# Linkable_LED_Matrix.net
KiCad netlist of a schematic drawn in EAGLE
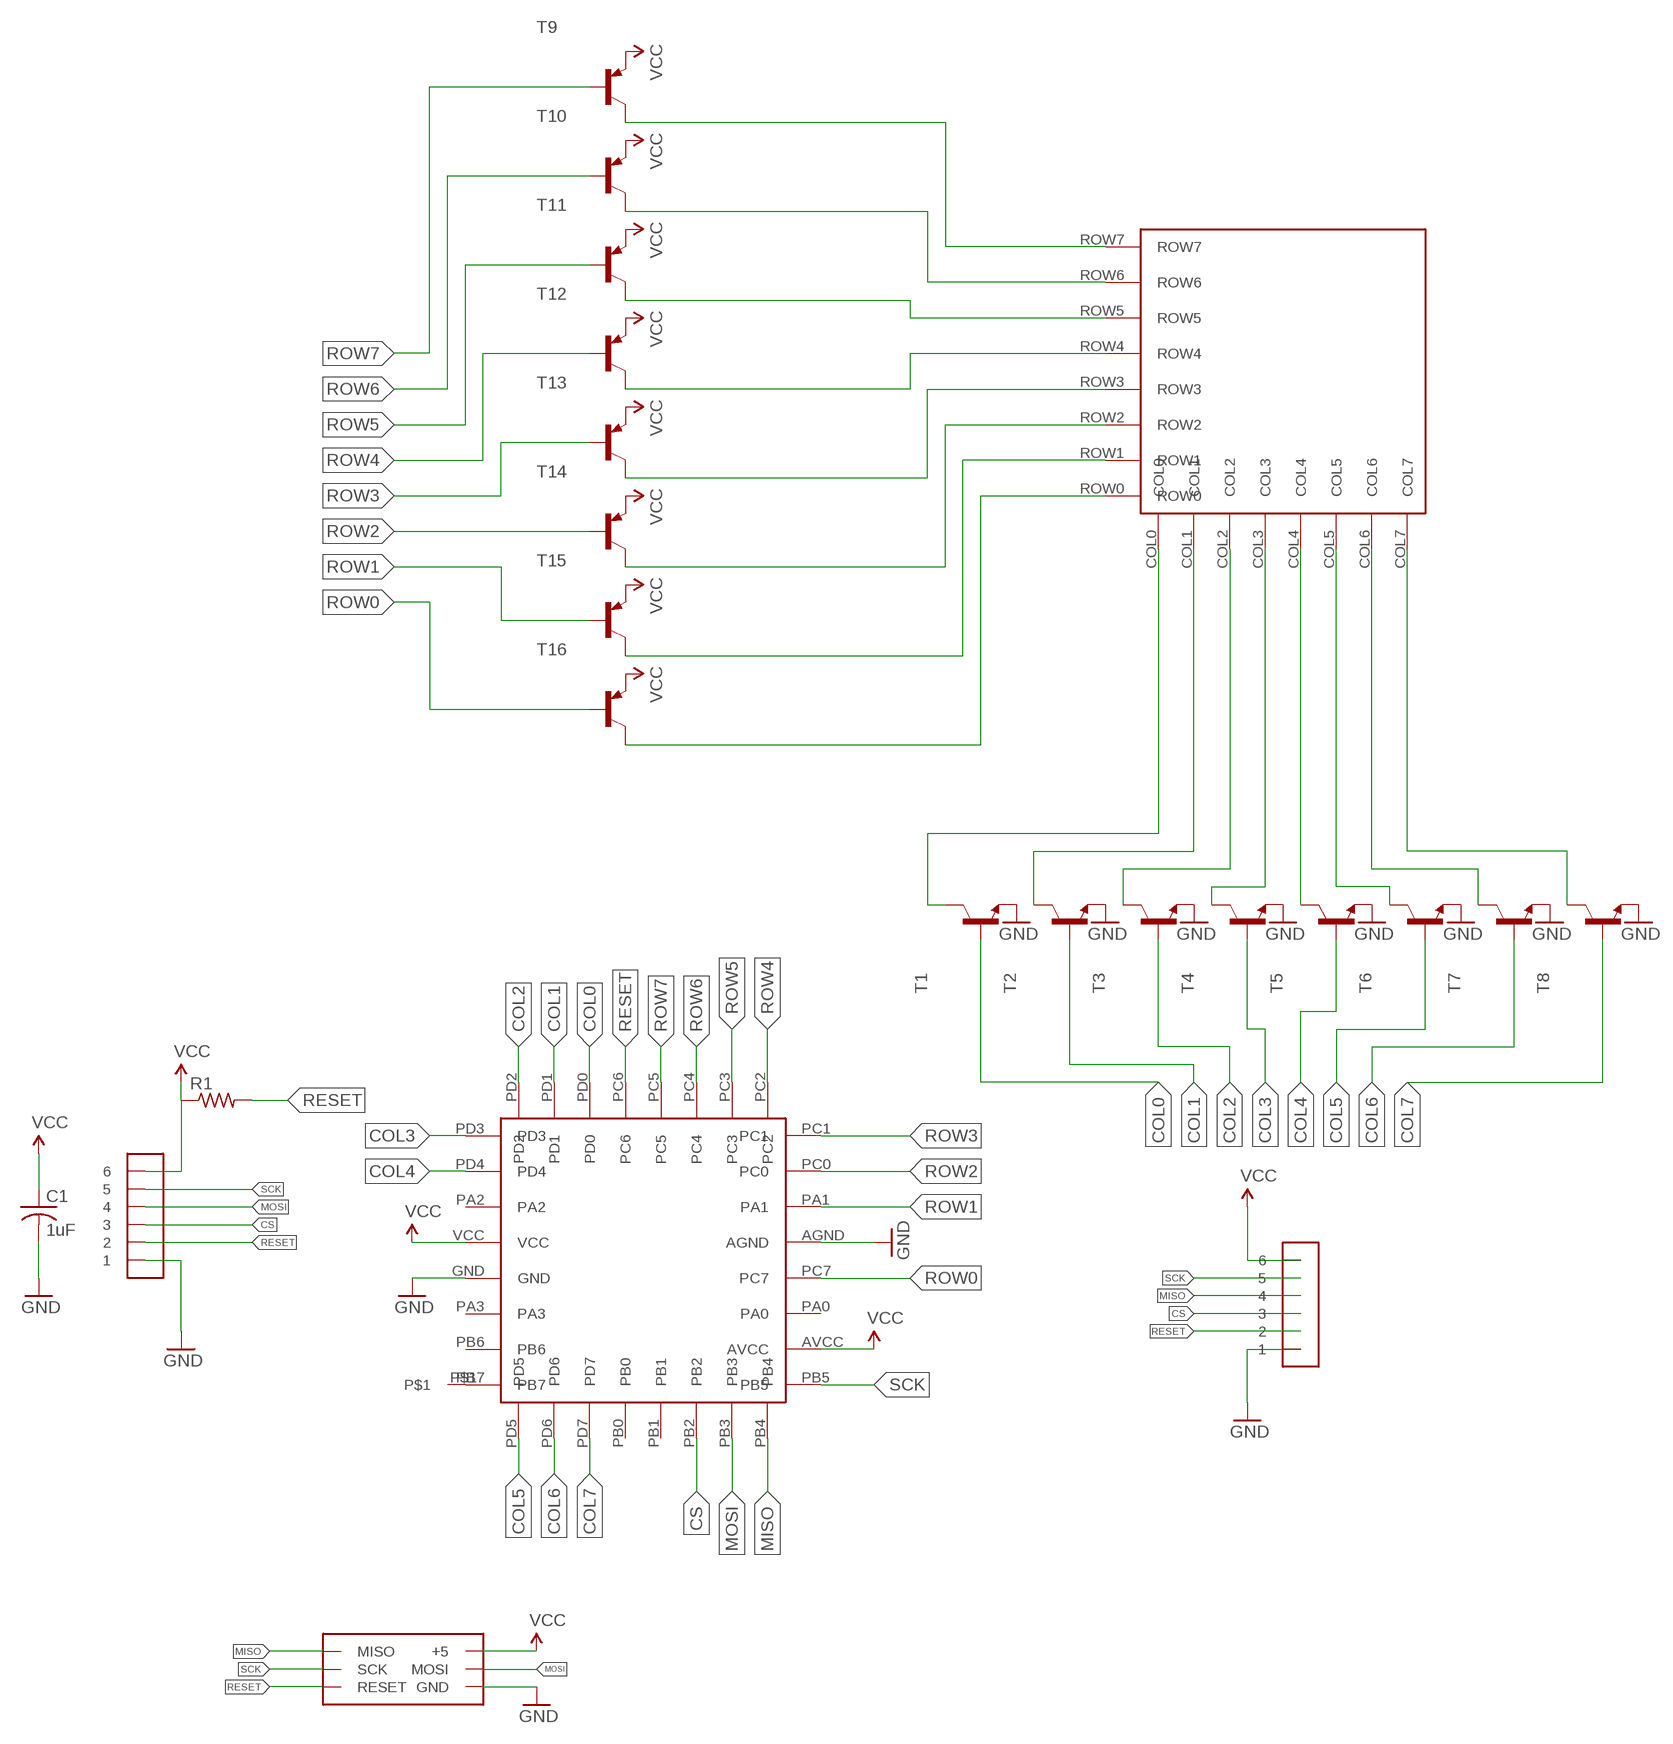
[diagram p0: schematic, sheet 1]

(export (version "E")
  (design (tool "Eeschema 10.0.6"))
  (components
    (comp (ref "C1")
      (value "1uF")
      (footprint "eagle-import:C0603")
      (libsource (lib "eagle-import") (part "C-USC0603"))
    )
    (comp (ref "R1")
      (value "R-US_R0603")
      (footprint "eagle-import:R0603")
      (libsource (lib "eagle-import") (part "R-US_R0603"))
    )
    (comp (ref "T1")
      (value "MMBT2222ALT1-NPN-SOT23-BEC")
      (footprint "eagle-import:SOT23-BEC")
      (libsource (lib "eagle-import") (part "-NPN-SOT23-BECMMBT2222ALT1"))
    )
    (comp (ref "T2")
      (value "MMBT2222ALT1-NPN-SOT23-BEC")
      (footprint "eagle-import:SOT23-BEC")
      (libsource (lib "eagle-import") (part "-NPN-SOT23-BECMMBT2222ALT1"))
    )
    (comp (ref "T3")
      (value "MMBT2222ALT1-NPN-SOT23-BEC")
      (footprint "eagle-import:SOT23-BEC")
      (libsource (lib "eagle-import") (part "-NPN-SOT23-BECMMBT2222ALT1"))
    )
    (comp (ref "T4")
      (value "MMBT2222ALT1-NPN-SOT23-BEC")
      (footprint "eagle-import:SOT23-BEC")
      (libsource (lib "eagle-import") (part "-NPN-SOT23-BECMMBT2222ALT1"))
    )
    (comp (ref "T5")
      (value "MMBT2222ALT1-NPN-SOT23-BEC")
      (footprint "eagle-import:SOT23-BEC")
      (libsource (lib "eagle-import") (part "-NPN-SOT23-BECMMBT2222ALT1"))
    )
    (comp (ref "T6")
      (value "MMBT2222ALT1-NPN-SOT23-BEC")
      (footprint "eagle-import:SOT23-BEC")
      (libsource (lib "eagle-import") (part "-NPN-SOT23-BECMMBT2222ALT1"))
    )
    (comp (ref "T7")
      (value "MMBT2222ALT1-NPN-SOT23-BEC")
      (footprint "eagle-import:SOT23-BEC")
      (libsource (lib "eagle-import") (part "-NPN-SOT23-BECMMBT2222ALT1"))
    )
    (comp (ref "T8")
      (value "MMBT2222ALT1-NPN-SOT23-BEC")
      (footprint "eagle-import:SOT23-BEC")
      (libsource (lib "eagle-import") (part "-NPN-SOT23-BECMMBT2222ALT1"))
    )
    (comp (ref "T9")
      (value "MMBT3906LT1-PNP-SOT23-BEC")
      (footprint "eagle-import:SOT23-BEC")
      (libsource (lib "eagle-import") (part "-PNP-SOT23-BECMMBT3906LT1"))
    )
    (comp (ref "T10")
      (value "MMBT3906LT1-PNP-SOT23-BEC")
      (footprint "eagle-import:SOT23-BEC")
      (libsource (lib "eagle-import") (part "-PNP-SOT23-BECMMBT3906LT1"))
    )
    (comp (ref "T11")
      (value "MMBT3906LT1-PNP-SOT23-BEC")
      (footprint "eagle-import:SOT23-BEC")
      (libsource (lib "eagle-import") (part "-PNP-SOT23-BECMMBT3906LT1"))
    )
    (comp (ref "T12")
      (value "MMBT3906LT1-PNP-SOT23-BEC")
      (footprint "eagle-import:SOT23-BEC")
      (libsource (lib "eagle-import") (part "-PNP-SOT23-BECMMBT3906LT1"))
    )
    (comp (ref "T13")
      (value "MMBT3906LT1-PNP-SOT23-BEC")
      (footprint "eagle-import:SOT23-BEC")
      (libsource (lib "eagle-import") (part "-PNP-SOT23-BECMMBT3906LT1"))
    )
    (comp (ref "T14")
      (value "MMBT3906LT1-PNP-SOT23-BEC")
      (footprint "eagle-import:SOT23-BEC")
      (libsource (lib "eagle-import") (part "-PNP-SOT23-BECMMBT3906LT1"))
    )
    (comp (ref "T15")
      (value "MMBT3906LT1-PNP-SOT23-BEC")
      (footprint "eagle-import:SOT23-BEC")
      (libsource (lib "eagle-import") (part "-PNP-SOT23-BECMMBT3906LT1"))
    )
    (comp (ref "T16")
      (value "MMBT3906LT1-PNP-SOT23-BEC")
      (footprint "eagle-import:SOT23-BEC")
      (libsource (lib "eagle-import") (part "-PNP-SOT23-BECMMBT3906LT1"))
    )
    (comp (ref "U$1")
      (value "ATTINY48")
      (footprint "eagle-import:ATTINY48")
      (libsource (lib "eagle-import") (part "ATTINY48"))
    )
    (comp (ref "U$3")
      (value "8X8_LED_MATRIX")
      (footprint "eagle-import:8X8_LED_MATRIX")
      (libsource (lib "eagle-import") (part "8X8_LED_MATRIX"))
    )
    (comp (ref "U$5")
      (value "1X1MM_PAD")
      (footprint "eagle-import:1X1MM_PAD")
      (libsource (lib "eagle-import") (part "1X1MM_PAD"))
    )
    (comp (ref "U$6")
      (value "DIP1X6MALE")
      (footprint "eagle-import:DIP1X6MALE")
      (libsource (lib "eagle-import") (part "DIP1X6MALE"))
    )
    (comp (ref "U$7")
      (value "DIP1X6MALE")
      (footprint "eagle-import:DIP1X6MALE")
      (libsource (lib "eagle-import") (part "DIP1X6MALE"))
    )
    (comp (ref "U$9")
      (value "DIP2X3MALE")
      (footprint "eagle-import:DIP2X3MALE")
      (libsource (lib "eagle-import") (part "DIP2X3MALE"))
    )
  )
  (nets
    (net (code "1") (name "COL0") (class "Default")
      (node (ref "T1") (pin "B") (pinfunction "B_B") (pintype "passive"))
      (node (ref "U$1") (pin "PD0") (pinfunction "PD0_PD0") (pintype "bidirectional"))
    )
    (net (code "2") (name "COL1") (class "Default")
      (node (ref "T2") (pin "B") (pinfunction "B_B") (pintype "passive"))
      (node (ref "U$1") (pin "PD1") (pinfunction "PD1_PD1") (pintype "bidirectional"))
    )
    (net (code "3") (name "COL2") (class "Default")
      (node (ref "T3") (pin "B") (pinfunction "B_B") (pintype "passive"))
      (node (ref "U$1") (pin "PD2") (pinfunction "PD2_PD2") (pintype "bidirectional"))
    )
    (net (code "4") (name "COL3") (class "Default")
      (node (ref "T4") (pin "B") (pinfunction "B_B") (pintype "passive"))
      (node (ref "U$1") (pin "PD3") (pinfunction "PD3_PD3") (pintype "bidirectional"))
    )
    (net (code "5") (name "COL4") (class "Default")
      (node (ref "T5") (pin "B") (pinfunction "B_B") (pintype "passive"))
      (node (ref "U$1") (pin "PD4") (pinfunction "PD4_PD4") (pintype "bidirectional"))
    )
    (net (code "6") (name "COL5") (class "Default")
      (node (ref "T6") (pin "B") (pinfunction "B_B") (pintype "passive"))
      (node (ref "U$1") (pin "PD5") (pinfunction "PD5_PD5") (pintype "bidirectional"))
    )
    (net (code "7") (name "COL6") (class "Default")
      (node (ref "T7") (pin "B") (pinfunction "B_B") (pintype "passive"))
      (node (ref "U$1") (pin "PD6") (pinfunction "PD6_PD6") (pintype "bidirectional"))
    )
    (net (code "8") (name "COL7") (class "Default")
      (node (ref "T8") (pin "B") (pinfunction "B_B") (pintype "passive"))
      (node (ref "U$1") (pin "PD7") (pinfunction "PD7_PD7") (pintype "bidirectional"))
    )
    (net (code "9") (name "CS") (class "Default")
      (node (ref "U$1") (pin "PB2") (pinfunction "PB2_PB2") (pintype "bidirectional"))
      (node (ref "U$6") (pin "3") (pinfunction "3_3") (pintype "bidirectional"))
      (node (ref "U$7") (pin "3") (pinfunction "3_3") (pintype "bidirectional"))
    )
    (net (code "10") (name "GND") (class "Default")
      (node (ref "C1") (pin "2") (pinfunction "2_2") (pintype "passive"))
      (node (ref "T1") (pin "E") (pinfunction "E_E") (pintype "passive"))
      (node (ref "T2") (pin "E") (pinfunction "E_E") (pintype "passive"))
      (node (ref "T3") (pin "E") (pinfunction "E_E") (pintype "passive"))
      (node (ref "T4") (pin "E") (pinfunction "E_E") (pintype "passive"))
      (node (ref "T5") (pin "E") (pinfunction "E_E") (pintype "passive"))
      (node (ref "T6") (pin "E") (pinfunction "E_E") (pintype "passive"))
      (node (ref "T7") (pin "E") (pinfunction "E_E") (pintype "passive"))
      (node (ref "T8") (pin "E") (pinfunction "E_E") (pintype "passive"))
      (node (ref "U$1") (pin "AGND") (pinfunction "AGND_AGND") (pintype "bidirectional"))
      (node (ref "U$1") (pin "GND") (pinfunction "GND_GND") (pintype "bidirectional"))
      (node (ref "U$6") (pin "1") (pinfunction "1_1") (pintype "bidirectional"))
      (node (ref "U$7") (pin "1") (pinfunction "1_1") (pintype "bidirectional"))
      (node (ref "U$9") (pin "GND") (pinfunction "GND_GND") (pintype "bidirectional"))
    )
    (net (code "11") (name "MISO") (class "Default")
      (node (ref "U$1") (pin "PB4") (pinfunction "PB4_PB4") (pintype "bidirectional"))
      (node (ref "U$7") (pin "4") (pinfunction "4_4") (pintype "bidirectional"))
      (node (ref "U$9") (pin "MISO") (pinfunction "MISO_MISO") (pintype "bidirectional"))
    )
    (net (code "12") (name "MOSI") (class "Default")
      (node (ref "U$1") (pin "PB3") (pinfunction "PB3_PB3") (pintype "bidirectional"))
      (node (ref "U$6") (pin "4") (pinfunction "4_4") (pintype "bidirectional"))
      (node (ref "U$9") (pin "MOSI") (pinfunction "MOSI_MOSI") (pintype "bidirectional"))
    )
    (net (code "13") (name "Net-(T1-PadC)") (class "Default")
      (node (ref "T1") (pin "C") (pinfunction "C_C") (pintype "passive"))
      (node (ref "U$3") (pin "COL0") (pinfunction "COL0_COL0") (pintype "bidirectional"))
    )
    (net (code "14") (name "Net-(T2-PadC)") (class "Default")
      (node (ref "T2") (pin "C") (pinfunction "C_C") (pintype "passive"))
      (node (ref "U$3") (pin "COL1") (pinfunction "COL1_COL1") (pintype "bidirectional"))
    )
    (net (code "15") (name "Net-(T3-PadC)") (class "Default")
      (node (ref "T3") (pin "C") (pinfunction "C_C") (pintype "passive"))
      (node (ref "U$3") (pin "COL2") (pinfunction "COL2_COL2") (pintype "bidirectional"))
    )
    (net (code "16") (name "Net-(T4-PadC)") (class "Default")
      (node (ref "T4") (pin "C") (pinfunction "C_C") (pintype "passive"))
      (node (ref "U$3") (pin "COL3") (pinfunction "COL3_COL3") (pintype "bidirectional"))
    )
    (net (code "17") (name "Net-(T5-PadC)") (class "Default")
      (node (ref "T5") (pin "C") (pinfunction "C_C") (pintype "passive"))
      (node (ref "U$3") (pin "COL4") (pinfunction "COL4_COL4") (pintype "bidirectional"))
    )
    (net (code "18") (name "Net-(T6-PadC)") (class "Default")
      (node (ref "T6") (pin "C") (pinfunction "C_C") (pintype "passive"))
      (node (ref "U$3") (pin "COL5") (pinfunction "COL5_COL5") (pintype "bidirectional"))
    )
    (net (code "19") (name "Net-(T7-PadC)") (class "Default")
      (node (ref "T7") (pin "C") (pinfunction "C_C") (pintype "passive"))
      (node (ref "U$3") (pin "COL6") (pinfunction "COL6_COL6") (pintype "bidirectional"))
    )
    (net (code "20") (name "Net-(T8-PadC)") (class "Default")
      (node (ref "T8") (pin "C") (pinfunction "C_C") (pintype "passive"))
      (node (ref "U$3") (pin "COL7") (pinfunction "COL7_COL7") (pintype "bidirectional"))
    )
    (net (code "21") (name "Net-(T9-PadC)") (class "Default")
      (node (ref "T9") (pin "C") (pinfunction "C_C") (pintype "passive"))
      (node (ref "U$3") (pin "ROW7") (pinfunction "ROW7_ROW7") (pintype "bidirectional"))
    )
    (net (code "22") (name "Net-(T10-PadC)") (class "Default")
      (node (ref "T10") (pin "C") (pinfunction "C_C") (pintype "passive"))
      (node (ref "U$3") (pin "ROW6") (pinfunction "ROW6_ROW6") (pintype "bidirectional"))
    )
    (net (code "23") (name "Net-(T11-PadC)") (class "Default")
      (node (ref "T11") (pin "C") (pinfunction "C_C") (pintype "passive"))
      (node (ref "U$3") (pin "ROW5") (pinfunction "ROW5_ROW5") (pintype "bidirectional"))
    )
    (net (code "24") (name "Net-(T12-PadC)") (class "Default")
      (node (ref "T12") (pin "C") (pinfunction "C_C") (pintype "passive"))
      (node (ref "U$3") (pin "ROW4") (pinfunction "ROW4_ROW4") (pintype "bidirectional"))
    )
    (net (code "25") (name "Net-(T13-PadC)") (class "Default")
      (node (ref "T13") (pin "C") (pinfunction "C_C") (pintype "passive"))
      (node (ref "U$3") (pin "ROW3") (pinfunction "ROW3_ROW3") (pintype "bidirectional"))
    )
    (net (code "26") (name "Net-(T14-PadC)") (class "Default")
      (node (ref "T14") (pin "C") (pinfunction "C_C") (pintype "passive"))
      (node (ref "U$3") (pin "ROW2") (pinfunction "ROW2_ROW2") (pintype "bidirectional"))
    )
    (net (code "27") (name "Net-(T15-PadC)") (class "Default")
      (node (ref "T15") (pin "C") (pinfunction "C_C") (pintype "passive"))
      (node (ref "U$3") (pin "ROW1") (pinfunction "ROW1_ROW1") (pintype "bidirectional"))
    )
    (net (code "28") (name "Net-(T16-PadC)") (class "Default")
      (node (ref "T16") (pin "C") (pinfunction "C_C") (pintype "passive"))
      (node (ref "U$3") (pin "ROW0") (pinfunction "ROW0_ROW0") (pintype "bidirectional"))
    )
    (net (code "29") (name "Net-(U$1-PadPB7)") (class "Default")
      (node (ref "U$1") (pin "PB7") (pinfunction "PB7_PB7") (pintype "bidirectional"))
      (node (ref "U$5") (pin "P$1") (pinfunction "P$1_P$1") (pintype "bidirectional"))
    )
    (net (code "30") (name "RESET") (class "Default")
      (node (ref "R1") (pin "2") (pinfunction "2_2") (pintype "passive"))
      (node (ref "U$1") (pin "PC6") (pinfunction "PC6_PC6") (pintype "bidirectional"))
      (node (ref "U$6") (pin "2") (pinfunction "2_2") (pintype "bidirectional"))
      (node (ref "U$7") (pin "2") (pinfunction "2_2") (pintype "bidirectional"))
      (node (ref "U$9") (pin "RESET") (pinfunction "RESET_RESET") (pintype "bidirectional"))
    )
    (net (code "31") (name "ROW0") (class "Default")
      (node (ref "T16") (pin "B") (pinfunction "B_B") (pintype "passive"))
      (node (ref "U$1") (pin "PC7") (pinfunction "PC7_PC7") (pintype "bidirectional"))
    )
    (net (code "32") (name "ROW1") (class "Default")
      (node (ref "T15") (pin "B") (pinfunction "B_B") (pintype "passive"))
      (node (ref "U$1") (pin "PA1") (pinfunction "PA1_PA1") (pintype "bidirectional"))
    )
    (net (code "33") (name "ROW2") (class "Default")
      (node (ref "T14") (pin "B") (pinfunction "B_B") (pintype "passive"))
      (node (ref "U$1") (pin "PC0") (pinfunction "PC0_PC0") (pintype "bidirectional"))
    )
    (net (code "34") (name "ROW3") (class "Default")
      (node (ref "T13") (pin "B") (pinfunction "B_B") (pintype "passive"))
      (node (ref "U$1") (pin "PC1") (pinfunction "PC1_PC1") (pintype "bidirectional"))
    )
    (net (code "35") (name "ROW4") (class "Default")
      (node (ref "T12") (pin "B") (pinfunction "B_B") (pintype "passive"))
      (node (ref "U$1") (pin "PC2") (pinfunction "PC2_PC2") (pintype "bidirectional"))
    )
    (net (code "36") (name "ROW5") (class "Default")
      (node (ref "T11") (pin "B") (pinfunction "B_B") (pintype "passive"))
      (node (ref "U$1") (pin "PC3") (pinfunction "PC3_PC3") (pintype "bidirectional"))
    )
    (net (code "37") (name "ROW6") (class "Default")
      (node (ref "T10") (pin "B") (pinfunction "B_B") (pintype "passive"))
      (node (ref "U$1") (pin "PC4") (pinfunction "PC4_PC4") (pintype "bidirectional"))
    )
    (net (code "38") (name "ROW7") (class "Default")
      (node (ref "T9") (pin "B") (pinfunction "B_B") (pintype "passive"))
      (node (ref "U$1") (pin "PC5") (pinfunction "PC5_PC5") (pintype "bidirectional"))
    )
    (net (code "39") (name "SCK") (class "Default")
      (node (ref "U$1") (pin "PB5") (pinfunction "PB5_PB5") (pintype "bidirectional"))
      (node (ref "U$6") (pin "5") (pinfunction "5_5") (pintype "bidirectional"))
      (node (ref "U$7") (pin "5") (pinfunction "5_5") (pintype "bidirectional"))
      (node (ref "U$9") (pin "SCK") (pinfunction "SCK_SCK") (pintype "bidirectional"))
    )
    (net (code "40") (name "VCC") (class "Default")
      (node (ref "C1") (pin "1") (pinfunction "1_1") (pintype "passive"))
      (node (ref "R1") (pin "1") (pinfunction "1_1") (pintype "passive"))
      (node (ref "T10") (pin "E") (pinfunction "E_E") (pintype "passive"))
      (node (ref "T11") (pin "E") (pinfunction "E_E") (pintype "passive"))
      (node (ref "T12") (pin "E") (pinfunction "E_E") (pintype "passive"))
      (node (ref "T13") (pin "E") (pinfunction "E_E") (pintype "passive"))
      (node (ref "T14") (pin "E") (pinfunction "E_E") (pintype "passive"))
      (node (ref "T15") (pin "E") (pinfunction "E_E") (pintype "passive"))
      (node (ref "T16") (pin "E") (pinfunction "E_E") (pintype "passive"))
      (node (ref "T9") (pin "E") (pinfunction "E_E") (pintype "passive"))
      (node (ref "U$1") (pin "AVCC") (pinfunction "AVCC_AVCC") (pintype "bidirectional"))
      (node (ref "U$1") (pin "VCC") (pinfunction "VCC_VCC") (pintype "bidirectional"))
      (node (ref "U$6") (pin "6") (pinfunction "6_6") (pintype "bidirectional"))
      (node (ref "U$7") (pin "6") (pinfunction "6_6") (pintype "bidirectional"))
      (node (ref "U$9") (pin "5V") (pinfunction "+5_5V") (pintype "bidirectional"))
    )
    (net (code "41") (name "unconnected-(U$1-PadPA0)") (class "Default")
      (node (ref "U$1") (pin "PA0") (pinfunction "PA0_PA0") (pintype "bidirectional"))
    )
    (net (code "42") (name "unconnected-(U$1-PadPA2)") (class "Default")
      (node (ref "U$1") (pin "PA2") (pinfunction "PA2_PA2") (pintype "bidirectional"))
    )
    (net (code "43") (name "unconnected-(U$1-PadPA3)") (class "Default")
      (node (ref "U$1") (pin "PA3") (pinfunction "PA3_PA3") (pintype "bidirectional"))
    )
    (net (code "44") (name "unconnected-(U$1-PadPB0)") (class "Default")
      (node (ref "U$1") (pin "PB0") (pinfunction "PB0_PB0") (pintype "bidirectional"))
    )
    (net (code "45") (name "unconnected-(U$1-PadPB1)") (class "Default")
      (node (ref "U$1") (pin "PB1") (pinfunction "PB1_PB1") (pintype "bidirectional"))
    )
    (net (code "46") (name "unconnected-(U$1-PadPB6)") (class "Default")
      (node (ref "U$1") (pin "PB6") (pinfunction "PB6_PB6") (pintype "bidirectional"))
    )
  )
)
